# BMP-Triangle.net
KiCad netlist of a schematic drawn in EAGLE
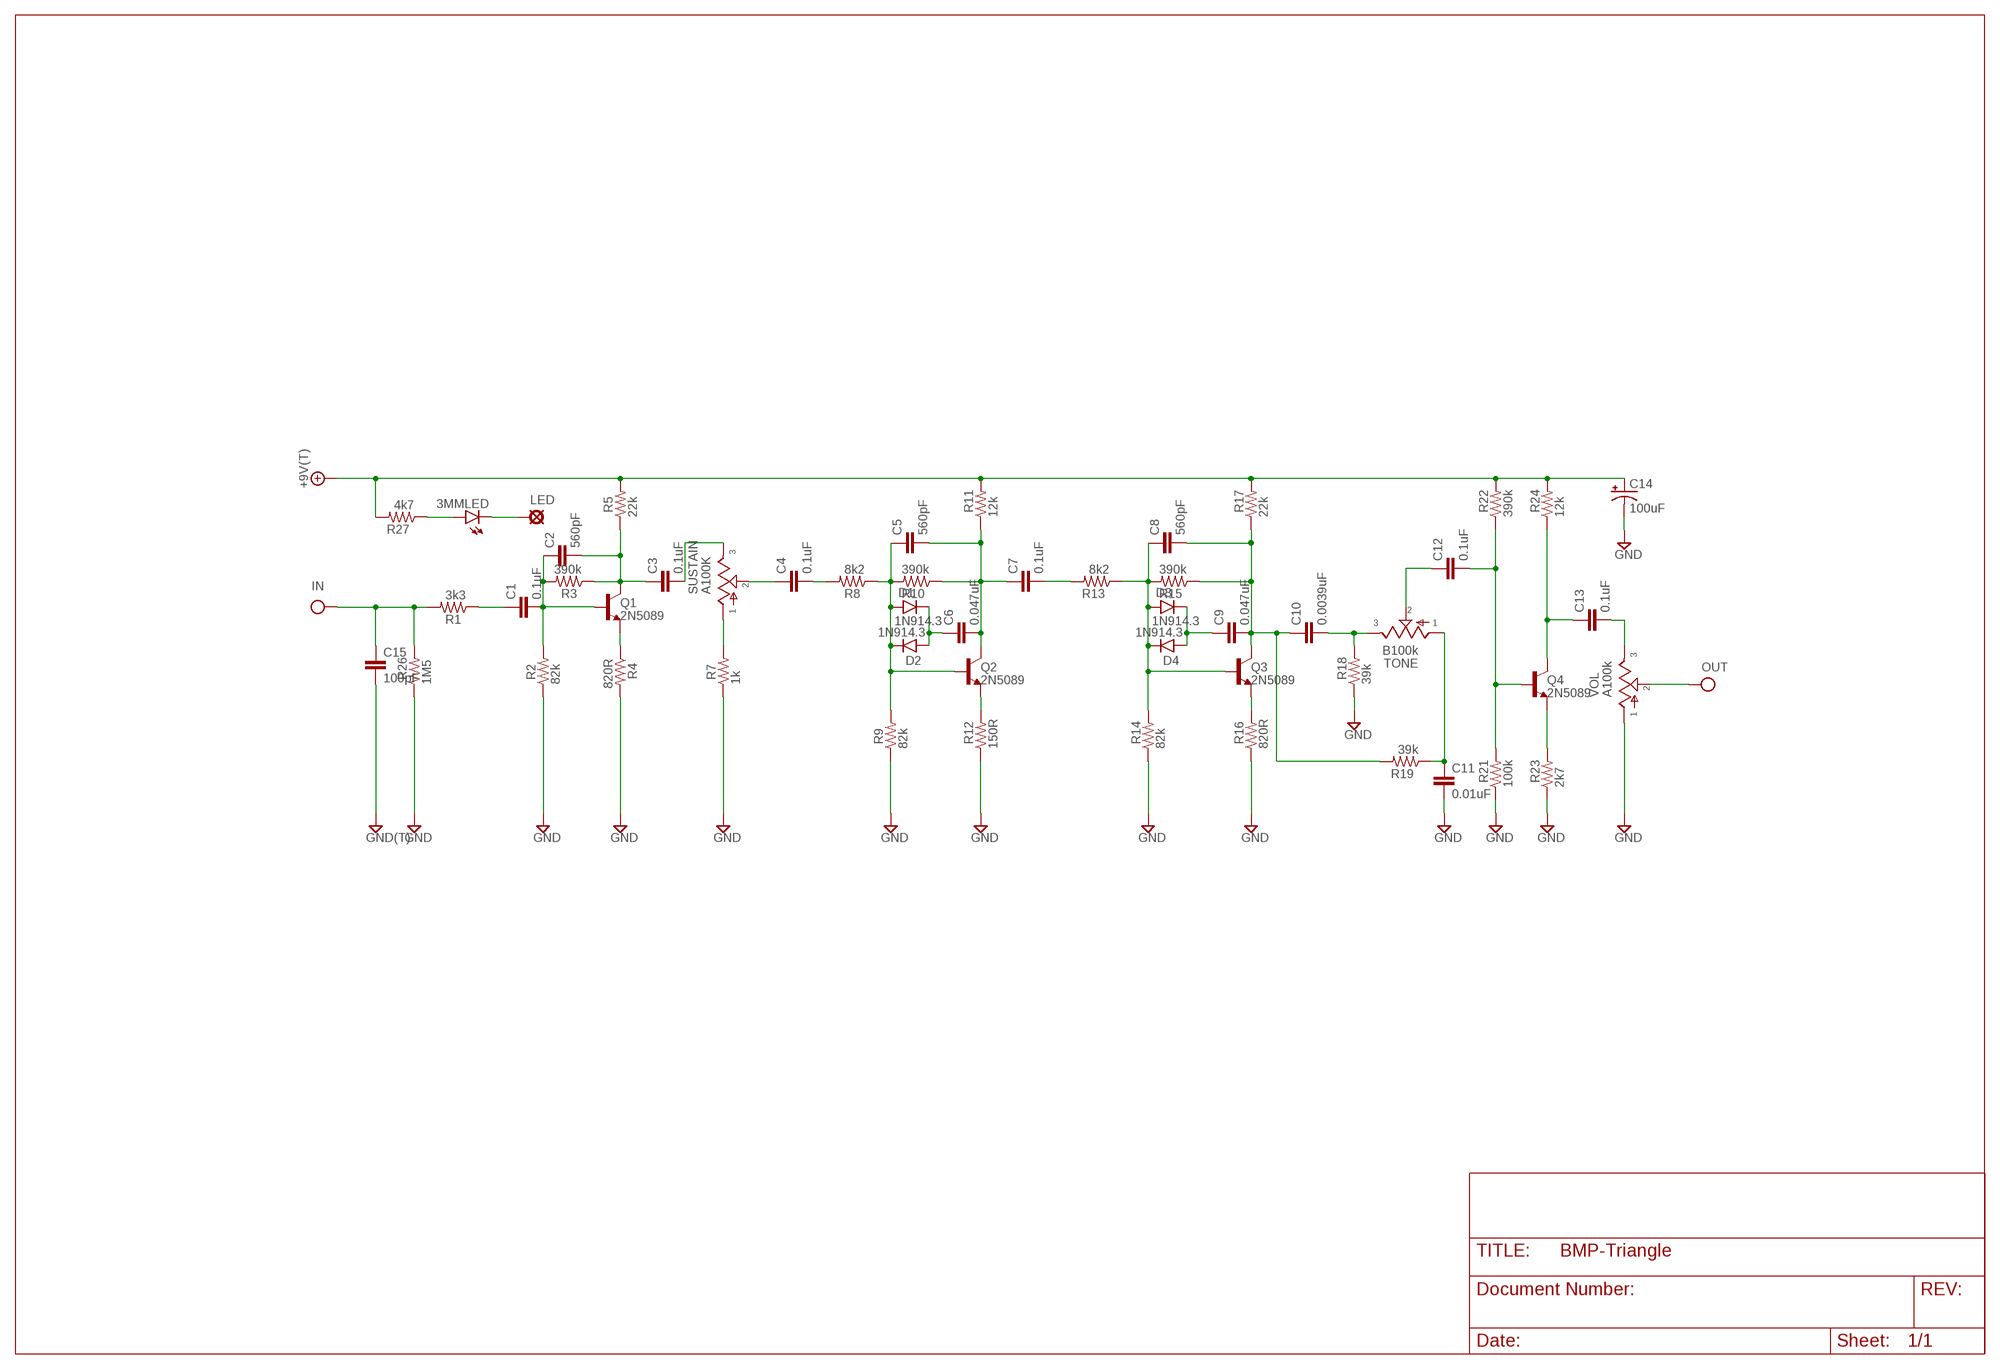
[diagram p0: schematic, sheet 1]

(export (version "E")
  (design (tool "Eeschema 10.0.6"))
  (components
    (comp (ref "+9V")
      (value "+9V(T)")
      (footprint "eagle-import:SQUARE")
      (libsource (lib "eagle-import") (part "+9V(T)"))
    )
    (comp (ref "3MMLED")
      (value "LED3MM")
      (footprint "eagle-import:LED3MM")
      (libsource (lib "eagle-import") (part "LED3MM"))
    )
    (comp (ref "C1")
      (value "0.1uF")
      (footprint "eagle-import:075X035")
      (libsource (lib "eagle-import") (part "075X0352"))
    )
    (comp (ref "C2")
      (value "560pF")
      (footprint "eagle-import:050X030_050_1")
      (libsource (lib "eagle-import") (part "050X030_0501"))
    )
    (comp (ref "C3")
      (value "0.1uF")
      (footprint "eagle-import:075X035")
      (libsource (lib "eagle-import") (part "075X0352"))
    )
    (comp (ref "C4")
      (value "0.1uF")
      (footprint "eagle-import:075X035")
      (libsource (lib "eagle-import") (part "075X0352"))
    )
    (comp (ref "C5")
      (value "560pF")
      (footprint "eagle-import:050X030_050_1")
      (libsource (lib "eagle-import") (part "050X030_0501"))
    )
    (comp (ref "C6")
      (value "0.047uF")
      (footprint "eagle-import:075X035")
      (libsource (lib "eagle-import") (part "075X0352"))
    )
    (comp (ref "C7")
      (value "0.1uF")
      (footprint "eagle-import:075X035")
      (libsource (lib "eagle-import") (part "075X0352"))
    )
    (comp (ref "C8")
      (value "560pF")
      (footprint "eagle-import:050X030_050_1")
      (libsource (lib "eagle-import") (part "050X030_0501"))
    )
    (comp (ref "C9")
      (value "0.047uF")
      (footprint "eagle-import:075X035")
      (libsource (lib "eagle-import") (part "075X0352"))
    )
    (comp (ref "C10")
      (value "0.0039uF")
      (footprint "eagle-import:075X035")
      (libsource (lib "eagle-import") (part "075X0352"))
    )
    (comp (ref "C11")
      (value "0.01uF")
      (footprint "eagle-import:075X035")
      (libsource (lib "eagle-import") (part "075X0352"))
    )
    (comp (ref "C12")
      (value "0.1uF")
      (footprint "eagle-import:075X035")
      (libsource (lib "eagle-import") (part "075X0352"))
    )
    (comp (ref "C13")
      (value "0.1uF")
      (footprint "eagle-import:075X035")
      (libsource (lib "eagle-import") (part "075X0352"))
    )
    (comp (ref "C14")
      (value "100uF")
      (footprint "eagle-import:063_025")
      (libsource (lib "eagle-import") (part "0631"))
    )
    (comp (ref "C15")
      (value "100pF")
      (footprint "eagle-import:050X030_050_1")
      (libsource (lib "eagle-import") (part "050X030_0501"))
    )
    (comp (ref "D1")
      (value "1N914.3")
      (footprint "eagle-import:DO35-3")
      (libsource (lib "eagle-import") (part "1N914.3"))
    )
    (comp (ref "D2")
      (value "1N914.3")
      (footprint "eagle-import:DO35-3")
      (libsource (lib "eagle-import") (part "1N914.3"))
    )
    (comp (ref "D3")
      (value "1N914.3")
      (footprint "eagle-import:DO35-3")
      (libsource (lib "eagle-import") (part "1N914.3"))
    )
    (comp (ref "D4")
      (value "1N914.3")
      (footprint "eagle-import:DO35-3")
      (libsource (lib "eagle-import") (part "1N914.3"))
    )
    (comp (ref "G")
      (value "GND(T)")
      (footprint "eagle-import:SQUARE")
      (libsource (lib "eagle-import") (part "GND(T)"))
    )
    (comp (ref "IN")
      (value "IN(T)")
      (footprint "eagle-import:SQUARE")
      (libsource (lib "eagle-import") (part "IN(T)"))
    )
    (comp (ref "LED")
      (value "PAD")
      (footprint "eagle-import:SQUARE")
      (libsource (lib "eagle-import") (part "PAD"))
    )
    (comp (ref "OUT")
      (value "OUT(T)")
      (footprint "eagle-import:SQUARE")
      (libsource (lib "eagle-import") (part "OUT(T)"))
    )
    (comp (ref "Q1")
      (value "2N5089")
      (footprint "eagle-import:TO92-")
      (libsource (lib "eagle-import") (part "2N5089"))
    )
    (comp (ref "Q2")
      (value "2N5089")
      (footprint "eagle-import:TO92-")
      (libsource (lib "eagle-import") (part "2N5089"))
    )
    (comp (ref "Q3")
      (value "2N5089")
      (footprint "eagle-import:TO92-")
      (libsource (lib "eagle-import") (part "2N5089"))
    )
    (comp (ref "Q4")
      (value "2N5089")
      (footprint "eagle-import:TO92-")
      (libsource (lib "eagle-import") (part "2N5089"))
    )
    (comp (ref "R1")
      (value "3k3")
      (footprint "eagle-import:R0207_3")
      (libsource (lib "eagle-import") (part "6MM.3"))
    )
    (comp (ref "R2")
      (value "82k")
      (footprint "eagle-import:R0207_3")
      (libsource (lib "eagle-import") (part "6MM.3"))
    )
    (comp (ref "R3")
      (value "390k")
      (footprint "eagle-import:R0207_3")
      (libsource (lib "eagle-import") (part "6MM.3"))
    )
    (comp (ref "R4")
      (value "820R")
      (footprint "eagle-import:R0207_3")
      (libsource (lib "eagle-import") (part "6MM.3"))
    )
    (comp (ref "R5")
      (value "22k")
      (footprint "eagle-import:R0207_3")
      (libsource (lib "eagle-import") (part "6MM.3"))
    )
    (comp (ref "R7")
      (value "1k")
      (footprint "eagle-import:R0207_3")
      (libsource (lib "eagle-import") (part "6MM.3"))
    )
    (comp (ref "R8")
      (value "8k2")
      (footprint "eagle-import:R0207_3")
      (libsource (lib "eagle-import") (part "6MM.3"))
    )
    (comp (ref "R9")
      (value "82k")
      (footprint "eagle-import:R0207_3")
      (libsource (lib "eagle-import") (part "6MM.3"))
    )
    (comp (ref "R10")
      (value "390k")
      (footprint "eagle-import:R0207_3")
      (libsource (lib "eagle-import") (part "6MM.3"))
    )
    (comp (ref "R11")
      (value "12k")
      (footprint "eagle-import:R0207_3")
      (libsource (lib "eagle-import") (part "6MM.3"))
    )
    (comp (ref "R12")
      (value "150R")
      (footprint "eagle-import:R0207_3")
      (libsource (lib "eagle-import") (part "6MM.3"))
    )
    (comp (ref "R13")
      (value "8k2")
      (footprint "eagle-import:R0207_3")
      (libsource (lib "eagle-import") (part "6MM.3"))
    )
    (comp (ref "R14")
      (value "82k")
      (footprint "eagle-import:R0207_3")
      (libsource (lib "eagle-import") (part "6MM.3"))
    )
    (comp (ref "R15")
      (value "390k")
      (footprint "eagle-import:R0207_3")
      (libsource (lib "eagle-import") (part "6MM.3"))
    )
    (comp (ref "R16")
      (value "820R")
      (footprint "eagle-import:R0207_3")
      (libsource (lib "eagle-import") (part "6MM.3"))
    )
    (comp (ref "R17")
      (value "22k")
      (footprint "eagle-import:R0207_3")
      (libsource (lib "eagle-import") (part "6MM.3"))
    )
    (comp (ref "R18")
      (value "39k")
      (footprint "eagle-import:R0207_3")
      (libsource (lib "eagle-import") (part "6MM.3"))
    )
    (comp (ref "R19")
      (value "39k")
      (footprint "eagle-import:R0207_3")
      (libsource (lib "eagle-import") (part "6MM.3"))
    )
    (comp (ref "R21")
      (value "100k")
      (footprint "eagle-import:R0207_3")
      (libsource (lib "eagle-import") (part "6MM.3"))
    )
    (comp (ref "R22")
      (value "390k")
      (footprint "eagle-import:R0207_3")
      (libsource (lib "eagle-import") (part "6MM.3"))
    )
    (comp (ref "R23")
      (value "2k7")
      (footprint "eagle-import:R0207_3")
      (libsource (lib "eagle-import") (part "6MM.3"))
    )
    (comp (ref "R24")
      (value "12k")
      (footprint "eagle-import:R0207_3")
      (libsource (lib "eagle-import") (part "6MM.3"))
    )
    (comp (ref "R26")
      (value "1M5")
      (footprint "eagle-import:R0207_3")
      (libsource (lib "eagle-import") (part "6MM.3"))
    )
    (comp (ref "R27")
      (value "4k7")
      (footprint "eagle-import:R0207_3")
      (libsource (lib "eagle-import") (part "6MM.3"))
    )
    (comp (ref "SUSTAIN")
      (value "A100K")
      (footprint "eagle-import:16MM_PCB_PADS")
      (libsource (lib "eagle-import") (part "POT16MM_PCB_PADS"))
    )
    (comp (ref "TONE")
      (value "B100k")
      (footprint "eagle-import:16MM_PCB_PADS")
      (libsource (lib "eagle-import") (part "POT16MM_PCB_PADS"))
    )
    (comp (ref "VOL")
      (value "A100k")
      (footprint "eagle-import:16MM_PCB_PADS")
      (libsource (lib "eagle-import") (part "POT16MM_PCB_PADS"))
    )
  )
  (nets
    (net (code "1") (name "+9V(T)") (class "Default")
      (node (ref "+9V") (pin "1") (pinfunction "+9V_1") (pintype "power_in"))
      (node (ref "C14") (pin "+") (pinfunction "+_+") (pintype "passive"))
      (node (ref "R11") (pin "2") (pinfunction "2_2") (pintype "passive"))
      (node (ref "R17") (pin "2") (pinfunction "2_2") (pintype "passive"))
      (node (ref "R22") (pin "2") (pinfunction "2_2") (pintype "passive"))
      (node (ref "R24") (pin "2") (pinfunction "2_2") (pintype "passive"))
      (node (ref "R27") (pin "2") (pinfunction "2_2") (pintype "passive"))
      (node (ref "R5") (pin "2") (pinfunction "2_2") (pintype "passive"))
    )
    (net (code "2") (name "GND") (class "Default")
      (node (ref "C11") (pin "2") (pinfunction "2_2") (pintype "passive"))
      (node (ref "C14") (pin "-") (pinfunction "-_-") (pintype "passive"))
      (node (ref "C15") (pin "2") (pinfunction "2_2") (pintype "passive"))
      (node (ref "G") (pin "1") (pinfunction "GND_1") (pintype "power_in"))
      (node (ref "R12") (pin "1") (pinfunction "1_1") (pintype "passive"))
      (node (ref "R14") (pin "1") (pinfunction "1_1") (pintype "passive"))
      (node (ref "R16") (pin "1") (pinfunction "1_1") (pintype "passive"))
      (node (ref "R18") (pin "1") (pinfunction "1_1") (pintype "passive"))
      (node (ref "R2") (pin "1") (pinfunction "1_1") (pintype "passive"))
      (node (ref "R21") (pin "1") (pinfunction "1_1") (pintype "passive"))
      (node (ref "R23") (pin "1") (pinfunction "1_1") (pintype "passive"))
      (node (ref "R26") (pin "1") (pinfunction "1_1") (pintype "passive"))
      (node (ref "R4") (pin "2") (pinfunction "2_2") (pintype "passive"))
      (node (ref "R7") (pin "1") (pinfunction "1_1") (pintype "passive"))
      (node (ref "R9") (pin "1") (pinfunction "1_1") (pintype "passive"))
      (node (ref "VOL") (pin "1") (pinfunction "1_1") (pintype "passive"))
    )
    (net (code "3") (name "IN(T)") (class "Default")
      (node (ref "C15") (pin "1") (pinfunction "1_1") (pintype "passive"))
      (node (ref "IN") (pin "1") (pinfunction "IN_1") (pintype "power_in"))
      (node (ref "R1") (pin "2") (pinfunction "2_2") (pintype "passive"))
      (node (ref "R26") (pin "2") (pinfunction "2_2") (pintype "passive"))
    )
    (net (code "4") (name "Net-(3MMLED-C)") (class "Default")
      (node (ref "3MMLED") (pin "K") (pinfunction "C_K") (pintype "passive"))
      (node (ref "LED") (pin "1") (pinfunction "PAD_1") (pintype "passive"))
    )
    (net (code "5") (name "Net-(3MMLED-PadA)") (class "Default")
      (node (ref "3MMLED") (pin "A") (pinfunction "A_A") (pintype "passive"))
      (node (ref "R27") (pin "1") (pinfunction "1_1") (pintype "passive"))
    )
    (net (code "6") (name "Net-(C1-Pad1)") (class "Default")
      (node (ref "C1") (pin "1") (pinfunction "1_1") (pintype "passive"))
      (node (ref "R1") (pin "1") (pinfunction "1_1") (pintype "passive"))
    )
    (net (code "7") (name "Net-(C3-Pad2)") (class "Default")
      (node (ref "C3") (pin "2") (pinfunction "2_2") (pintype "passive"))
      (node (ref "SUSTAIN") (pin "3") (pinfunction "3_3") (pintype "passive"))
    )
    (net (code "8") (name "Net-(C4-Pad1)") (class "Default")
      (node (ref "C4") (pin "1") (pinfunction "1_1") (pintype "passive"))
      (node (ref "SUSTAIN") (pin "2") (pinfunction "2_2") (pintype "passive"))
    )
    (net (code "9") (name "Net-(C4-Pad2)") (class "Default")
      (node (ref "C4") (pin "2") (pinfunction "2_2") (pintype "passive"))
      (node (ref "R8") (pin "2") (pinfunction "2_2") (pintype "passive"))
    )
    (net (code "10") (name "Net-(C6-Pad1)") (class "Default")
      (node (ref "C6") (pin "1") (pinfunction "1_1") (pintype "passive"))
      (node (ref "D1") (pin "C") (pinfunction "C_C") (pintype "passive"))
      (node (ref "D2") (pin "A") (pinfunction "A_A") (pintype "passive"))
    )
    (net (code "11") (name "Net-(C7-Pad2)") (class "Default")
      (node (ref "C7") (pin "2") (pinfunction "2_2") (pintype "passive"))
      (node (ref "R13") (pin "2") (pinfunction "2_2") (pintype "passive"))
    )
    (net (code "12") (name "Net-(C9-Pad1)") (class "Default")
      (node (ref "C9") (pin "1") (pinfunction "1_1") (pintype "passive"))
      (node (ref "D3") (pin "C") (pinfunction "C_C") (pintype "passive"))
      (node (ref "D4") (pin "A") (pinfunction "A_A") (pintype "passive"))
    )
    (net (code "13") (name "Net-(C10-Pad2)") (class "Default")
      (node (ref "C10") (pin "2") (pinfunction "2_2") (pintype "passive"))
      (node (ref "R18") (pin "2") (pinfunction "2_2") (pintype "passive"))
      (node (ref "TONE") (pin "3") (pinfunction "3_3") (pintype "passive"))
    )
    (net (code "14") (name "Net-(C11-Pad1)") (class "Default")
      (node (ref "C11") (pin "1") (pinfunction "1_1") (pintype "passive"))
      (node (ref "R19") (pin "1") (pinfunction "1_1") (pintype "passive"))
      (node (ref "TONE") (pin "1") (pinfunction "1_1") (pintype "passive"))
    )
    (net (code "15") (name "Net-(C12-Pad1)") (class "Default")
      (node (ref "C12") (pin "1") (pinfunction "1_1") (pintype "passive"))
      (node (ref "TONE") (pin "2") (pinfunction "2_2") (pintype "passive"))
    )
    (net (code "16") (name "Net-(C13-Pad2)") (class "Default")
      (node (ref "C13") (pin "2") (pinfunction "2_2") (pintype "passive"))
      (node (ref "VOL") (pin "3") (pinfunction "3_3") (pintype "passive"))
    )
    (net (code "17") (name "Net-(Q1-B)") (class "Default")
      (node (ref "C1") (pin "2") (pinfunction "2_2") (pintype "passive"))
      (node (ref "C2") (pin "1") (pinfunction "1_1") (pintype "passive"))
      (node (ref "Q1") (pin "2") (pinfunction "B_2") (pintype "passive"))
      (node (ref "R2") (pin "2") (pinfunction "2_2") (pintype "passive"))
      (node (ref "R3") (pin "2") (pinfunction "2_2") (pintype "passive"))
    )
    (net (code "18") (name "Net-(Q1-C)") (class "Default")
      (node (ref "C2") (pin "2") (pinfunction "2_2") (pintype "passive"))
      (node (ref "C3") (pin "1") (pinfunction "1_1") (pintype "passive"))
      (node (ref "Q1") (pin "1") (pinfunction "C_1") (pintype "passive"))
      (node (ref "R3") (pin "1") (pinfunction "1_1") (pintype "passive"))
      (node (ref "R5") (pin "1") (pinfunction "1_1") (pintype "passive"))
    )
    (net (code "19") (name "Net-(Q1-E)") (class "Default")
      (node (ref "Q1") (pin "3") (pinfunction "E_3") (pintype "passive"))
      (node (ref "R4") (pin "1") (pinfunction "1_1") (pintype "passive"))
    )
    (net (code "20") (name "Net-(Q2-B)") (class "Default")
      (node (ref "C5") (pin "1") (pinfunction "1_1") (pintype "passive"))
      (node (ref "D1") (pin "A") (pinfunction "A_A") (pintype "passive"))
      (node (ref "D2") (pin "C") (pinfunction "C_C") (pintype "passive"))
      (node (ref "Q2") (pin "2") (pinfunction "B_2") (pintype "passive"))
      (node (ref "R10") (pin "2") (pinfunction "2_2") (pintype "passive"))
      (node (ref "R8") (pin "1") (pinfunction "1_1") (pintype "passive"))
      (node (ref "R9") (pin "2") (pinfunction "2_2") (pintype "passive"))
    )
    (net (code "21") (name "Net-(Q2-C)") (class "Default")
      (node (ref "C5") (pin "2") (pinfunction "2_2") (pintype "passive"))
      (node (ref "C6") (pin "2") (pinfunction "2_2") (pintype "passive"))
      (node (ref "C7") (pin "1") (pinfunction "1_1") (pintype "passive"))
      (node (ref "Q2") (pin "1") (pinfunction "C_1") (pintype "passive"))
      (node (ref "R10") (pin "1") (pinfunction "1_1") (pintype "passive"))
      (node (ref "R11") (pin "1") (pinfunction "1_1") (pintype "passive"))
    )
    (net (code "22") (name "Net-(Q2-E)") (class "Default")
      (node (ref "Q2") (pin "3") (pinfunction "E_3") (pintype "passive"))
      (node (ref "R12") (pin "2") (pinfunction "2_2") (pintype "passive"))
    )
    (net (code "23") (name "Net-(Q3-B)") (class "Default")
      (node (ref "C8") (pin "1") (pinfunction "1_1") (pintype "passive"))
      (node (ref "D3") (pin "A") (pinfunction "A_A") (pintype "passive"))
      (node (ref "D4") (pin "C") (pinfunction "C_C") (pintype "passive"))
      (node (ref "Q3") (pin "2") (pinfunction "B_2") (pintype "passive"))
      (node (ref "R13") (pin "1") (pinfunction "1_1") (pintype "passive"))
      (node (ref "R14") (pin "2") (pinfunction "2_2") (pintype "passive"))
      (node (ref "R15") (pin "2") (pinfunction "2_2") (pintype "passive"))
    )
    (net (code "24") (name "Net-(Q3-C)") (class "Default")
      (node (ref "C10") (pin "1") (pinfunction "1_1") (pintype "passive"))
      (node (ref "C8") (pin "2") (pinfunction "2_2") (pintype "passive"))
      (node (ref "C9") (pin "2") (pinfunction "2_2") (pintype "passive"))
      (node (ref "Q3") (pin "1") (pinfunction "C_1") (pintype "passive"))
      (node (ref "R15") (pin "1") (pinfunction "1_1") (pintype "passive"))
      (node (ref "R17") (pin "1") (pinfunction "1_1") (pintype "passive"))
      (node (ref "R19") (pin "2") (pinfunction "2_2") (pintype "passive"))
    )
    (net (code "25") (name "Net-(Q3-E)") (class "Default")
      (node (ref "Q3") (pin "3") (pinfunction "E_3") (pintype "passive"))
      (node (ref "R16") (pin "2") (pinfunction "2_2") (pintype "passive"))
    )
    (net (code "26") (name "Net-(Q4-B)") (class "Default")
      (node (ref "C12") (pin "2") (pinfunction "2_2") (pintype "passive"))
      (node (ref "Q4") (pin "2") (pinfunction "B_2") (pintype "passive"))
      (node (ref "R21") (pin "2") (pinfunction "2_2") (pintype "passive"))
      (node (ref "R22") (pin "1") (pinfunction "1_1") (pintype "passive"))
    )
    (net (code "27") (name "Net-(Q4-C)") (class "Default")
      (node (ref "C13") (pin "1") (pinfunction "1_1") (pintype "passive"))
      (node (ref "Q4") (pin "1") (pinfunction "C_1") (pintype "passive"))
      (node (ref "R24") (pin "1") (pinfunction "1_1") (pintype "passive"))
    )
    (net (code "28") (name "Net-(Q4-E)") (class "Default")
      (node (ref "Q4") (pin "3") (pinfunction "E_3") (pintype "passive"))
      (node (ref "R23") (pin "2") (pinfunction "2_2") (pintype "passive"))
    )
    (net (code "29") (name "Net-(R7-Pad2)") (class "Default")
      (node (ref "R7") (pin "2") (pinfunction "2_2") (pintype "passive"))
      (node (ref "SUSTAIN") (pin "1") (pinfunction "1_1") (pintype "passive"))
    )
    (net (code "30") (name "OUT(T)") (class "Default")
      (node (ref "OUT") (pin "1") (pinfunction "OUT_1") (pintype "power_in"))
      (node (ref "VOL") (pin "2") (pinfunction "2_2") (pintype "passive"))
    )
  )
)
